# TEMP_NC_I2C_V2.net
KiCad netlist of a schematic drawn in EAGLE
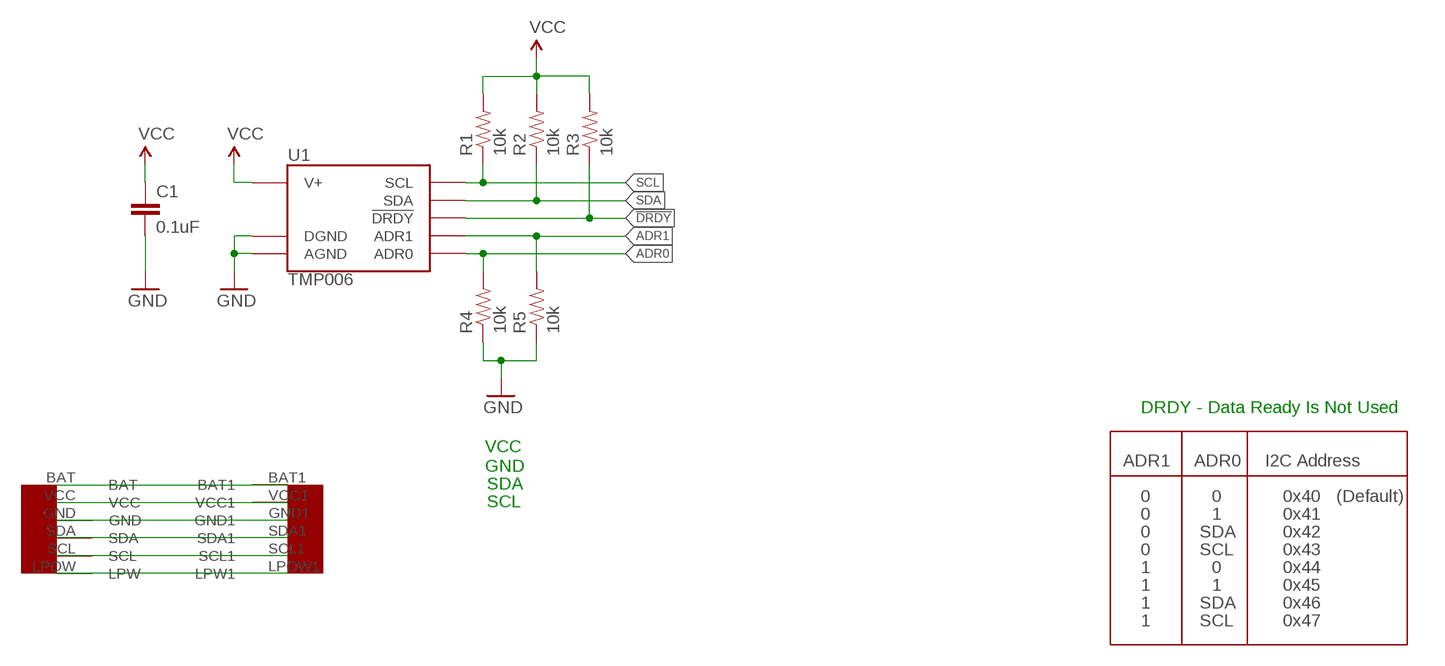
[diagram p0: schematic, sheet 1]

(export (version "E")
  (design (tool "Eeschema 10.0.6"))
  (components
    (comp (ref "C1")
      (value "0.1uF")
      (footprint "eagle-import:0603-CAP")
      (libsource (lib "eagle-import") (part "CAP0603-CAP"))
    )
    (comp (ref "R1")
      (value "10k")
      (footprint "eagle-import:0603-RES")
      (libsource (lib "eagle-import") (part "RESISTOR0603-RES"))
    )
    (comp (ref "R2")
      (value "10k")
      (footprint "eagle-import:0603-RES")
      (libsource (lib "eagle-import") (part "RESISTOR0603-RES"))
    )
    (comp (ref "R3")
      (value "10k")
      (footprint "eagle-import:0603-RES")
      (libsource (lib "eagle-import") (part "RESISTOR0603-RES"))
    )
    (comp (ref "R4")
      (value "10k")
      (footprint "eagle-import:0603-RES")
      (libsource (lib "eagle-import") (part "RESISTOR0603-RES"))
    )
    (comp (ref "R5")
      (value "10k")
      (footprint "eagle-import:0603-RES")
      (libsource (lib "eagle-import") (part "RESISTOR0603-RES"))
    )
    (comp (ref "U$1")
      (value "EZ-I2CHEADERV1")
      (footprint "eagle-import:EZ-I2CHEADERV1")
      (libsource (lib "eagle-import") (part "EZ-I2CHEADERV1"))
    )
    (comp (ref "U1")
      (value "TMP006")
      (footprint "eagle-import:BGA8DS")
      (libsource (lib "eagle-import") (part "TMP006"))
    )
  )
  (nets
    (net (code "1") (name "/~{DRDY}") (class "Default")
      (node (ref "R3") (pin "1") (pinfunction "1_1") (pintype "passive"))
      (node (ref "U1") (pin "C2") (pinfunction "~{DRDY}_C2") (pintype "bidirectional"))
    )
    (net (code "2") (name "ADR0") (class "Default")
      (node (ref "R4") (pin "2") (pinfunction "2_2") (pintype "passive"))
      (node (ref "U1") (pin "C1") (pinfunction "ADR0_C1") (pintype "bidirectional"))
    )
    (net (code "3") (name "ADR1") (class "Default")
      (node (ref "R5") (pin "2") (pinfunction "2_2") (pintype "passive"))
      (node (ref "U1") (pin "B1") (pinfunction "ADR1_B1") (pintype "bidirectional"))
    )
    (net (code "4") (name "GND") (class "Default")
      (node (ref "C1") (pin "2") (pinfunction "2_2") (pintype "passive"))
      (node (ref "R4") (pin "1") (pinfunction "1_1") (pintype "passive"))
      (node (ref "R5") (pin "1") (pinfunction "1_1") (pintype "passive"))
      (node (ref "U$1") (pin "GND") (pinfunction "GND_GND") (pintype "bidirectional"))
      (node (ref "U$1") (pin "GND1") (pinfunction "GND1_GND1") (pintype "bidirectional"))
      (node (ref "U1") (pin "A1") (pinfunction "DGND_A1") (pintype "bidirectional"))
      (node (ref "U1") (pin "A2") (pinfunction "AGND_A2") (pintype "bidirectional"))
    )
    (net (code "5") (name "Net-(U$1-LPW)") (class "Default")
      (node (ref "U$1") (pin "LPOW") (pinfunction "LPW_LPOW") (pintype "bidirectional"))
      (node (ref "U$1") (pin "LPOW1") (pinfunction "LPW1_LPOW1") (pintype "bidirectional"))
    )
    (net (code "6") (name "Net-(U$1-PadBAT)") (class "Default")
      (node (ref "U$1") (pin "BAT") (pinfunction "BAT_BAT") (pintype "bidirectional"))
      (node (ref "U$1") (pin "BAT1") (pinfunction "BAT1_BAT1") (pintype "bidirectional"))
    )
    (net (code "7") (name "SCL") (class "Default")
      (node (ref "R1") (pin "1") (pinfunction "1_1") (pintype "passive"))
      (node (ref "U$1") (pin "SCL") (pinfunction "SCL_SCL") (pintype "bidirectional"))
      (node (ref "U$1") (pin "SCL1") (pinfunction "SCL1_SCL1") (pintype "bidirectional"))
      (node (ref "U1") (pin "B3") (pinfunction "SCL_B3") (pintype "bidirectional"))
    )
    (net (code "8") (name "SDA") (class "Default")
      (node (ref "R2") (pin "1") (pinfunction "1_1") (pintype "passive"))
      (node (ref "U$1") (pin "SDA") (pinfunction "SDA_SDA") (pintype "bidirectional"))
      (node (ref "U$1") (pin "SDA1") (pinfunction "SDA1_SDA1") (pintype "bidirectional"))
      (node (ref "U1") (pin "C3") (pinfunction "SDA_C3") (pintype "bidirectional"))
    )
    (net (code "9") (name "VCC") (class "Default")
      (node (ref "C1") (pin "1") (pinfunction "1_1") (pintype "passive"))
      (node (ref "R1") (pin "2") (pinfunction "2_2") (pintype "passive"))
      (node (ref "R2") (pin "2") (pinfunction "2_2") (pintype "passive"))
      (node (ref "R3") (pin "2") (pinfunction "2_2") (pintype "passive"))
      (node (ref "U$1") (pin "VCC") (pinfunction "VCC_VCC") (pintype "bidirectional"))
      (node (ref "U$1") (pin "VCC1") (pinfunction "VCC1_VCC1") (pintype "bidirectional"))
      (node (ref "U1") (pin "A3") (pinfunction "V+_A3") (pintype "bidirectional"))
    )
  )
)
